# Esquematico.net
KiCad netlist of a schematic drawn in Altium Designer
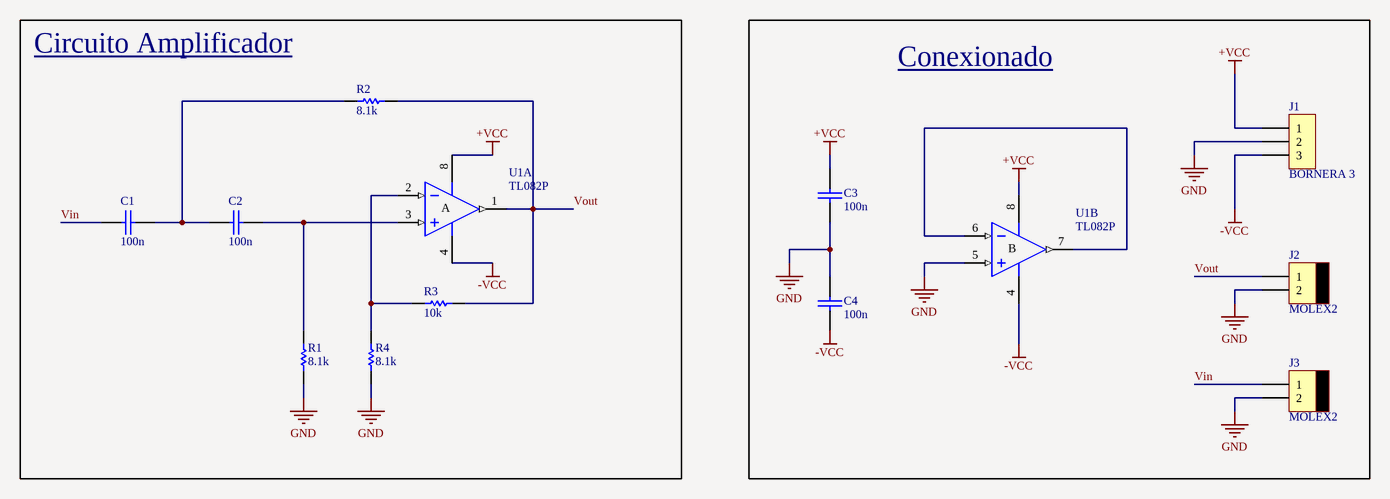
[diagram p0: Esquematico.SchDoc]

(export (version "E")
  (design (tool "Eeschema 10.0.6"))
  (components
    (comp (ref "C1") (value "100n") (footprint "CAP200") (libsource (lib "LIB PIO IX") (part "CAP")))
    (comp (ref "C2") (value "100n") (footprint "CAP200") (libsource (lib "LIB PIO IX") (part "CAP")))
    (comp (ref "C3") (value "100n") (footprint "CAP200") (libsource (lib "LIB PIO IX") (part "CAP")))
    (comp (ref "C4") (value "100n") (footprint "CAP200") (libsource (lib "LIB PIO IX") (part "CAP")))
    (comp (ref "J1")
      (value "BORNERA 3")
      (footprint "BORNERA3")
      (libsource (lib "LIB PIO IX") (part "BORNERA 3"))
    )
    (comp (ref "J2") (value "MOLEX2") (footprint "MOLEX2") (libsource (lib "LIB PIO IX") (part "MOLEX2")))
    (comp (ref "J3") (value "MOLEX2") (footprint "MOLEX2") (libsource (lib "LIB PIO IX") (part "MOLEX2")))
    (comp (ref "R1") (value "8.1k") (footprint "RES400") (libsource (lib "LIB PIO IX") (part "RES")))
    (comp (ref "R2") (value "8.1k") (footprint "RES400") (libsource (lib "LIB PIO IX") (part "RES")))
    (comp (ref "R3") (value "10k") (footprint "RES400") (libsource (lib "LIB PIO IX") (part "RES")))
    (comp (ref "R4") (value "8.1k") (footprint "RES400") (libsource (lib "LIB PIO IX") (part "RES")))
    (comp (ref "U1")
      (value "TL082P")
      (footprint "P008")
      (description "JFET-Input Operational Amplifier")
      (fields (field (name "PUBLISHER") "Altium Limited"))
      (libsource (lib "TI Operational Amplifier") (part "TL082P"))
    )
  )
  (nets
    (net (code "1") (name "+VCC") (class "Default")
      (node (ref "C3") (pin "2") (pinfunction "2_2") (pintype "passive"))
      (node (ref "J1") (pin "1") (pinfunction "1_1") (pintype "passive"))
      (node (ref "U1") (pin "8") (pinfunction "V+_8") (pintype "power_in"))
    )
    (net (code "2") (name "-VCC") (class "Default")
      (node (ref "C4") (pin "1") (pinfunction "1_1") (pintype "passive"))
      (node (ref "J1") (pin "3") (pinfunction "3_3") (pintype "passive"))
      (node (ref "U1") (pin "4") (pinfunction "V-_4") (pintype "power_in"))
    )
    (net (code "3") (name "/Vin") (class "Default")
      (node (ref "C1") (pin "1") (pinfunction "1_1") (pintype "passive"))
      (node (ref "J3") (pin "1") (pinfunction "1_1") (pintype "passive"))
    )
    (net (code "4") (name "/Vout") (class "Default")
      (node (ref "J2") (pin "1") (pinfunction "1_1") (pintype "passive"))
      (node (ref "R2") (pin "1") (pinfunction "1_1") (pintype "passive"))
      (node (ref "R3") (pin "1") (pinfunction "1_1") (pintype "passive"))
      (node (ref "U1") (pin "1") (pinfunction "OUT_1") (pintype "output"))
    )
    (net (code "5") (name "GND") (class "Default")
      (node (ref "C3") (pin "1") (pinfunction "1_1") (pintype "passive"))
      (node (ref "C4") (pin "2") (pinfunction "2_2") (pintype "passive"))
      (node (ref "J1") (pin "2") (pinfunction "2_2") (pintype "passive"))
      (node (ref "J2") (pin "2") (pinfunction "2_2") (pintype "passive"))
      (node (ref "J3") (pin "2") (pinfunction "2_2") (pintype "passive"))
      (node (ref "R1") (pin "1") (pinfunction "1_1") (pintype "passive"))
      (node (ref "R4") (pin "1") (pinfunction "1_1") (pintype "passive"))
      (node (ref "U1") (pin "5") (pinfunction "IN+_5") (pintype "input"))
    )
    (net (code "6") (name "Net-(C1-Pad2)") (class "Default")
      (node (ref "C1") (pin "2") (pinfunction "2_2") (pintype "passive"))
      (node (ref "C2") (pin "1") (pinfunction "1_1") (pintype "passive"))
      (node (ref "R2") (pin "2") (pinfunction "2_2") (pintype "passive"))
    )
    (net (code "7") (name "Net-(U1A-IN+)") (class "Default")
      (node (ref "C2") (pin "2") (pinfunction "2_2") (pintype "passive"))
      (node (ref "R1") (pin "2") (pinfunction "2_2") (pintype "passive"))
      (node (ref "U1") (pin "3") (pinfunction "IN+_3") (pintype "input"))
    )
    (net (code "8") (name "Net-(U1A-IN-)") (class "Default")
      (node (ref "R3") (pin "2") (pinfunction "2_2") (pintype "passive"))
      (node (ref "R4") (pin "2") (pinfunction "2_2") (pintype "passive"))
      (node (ref "U1") (pin "2") (pinfunction "IN-_2") (pintype "input"))
    )
    (net (code "9") (name "Net-(U1B-IN-)") (class "Default")
      (node (ref "U1") (pin "6") (pinfunction "IN-_6") (pintype "input"))
      (node (ref "U1") (pin "7") (pinfunction "OUT_7") (pintype "output"))
    )
  )
)
